# S7CAS-PLEIADES-CARTE-MERE_Pxx_FPGA_bank0.net
KiCad netlist of a schematic drawn in Altium Designer
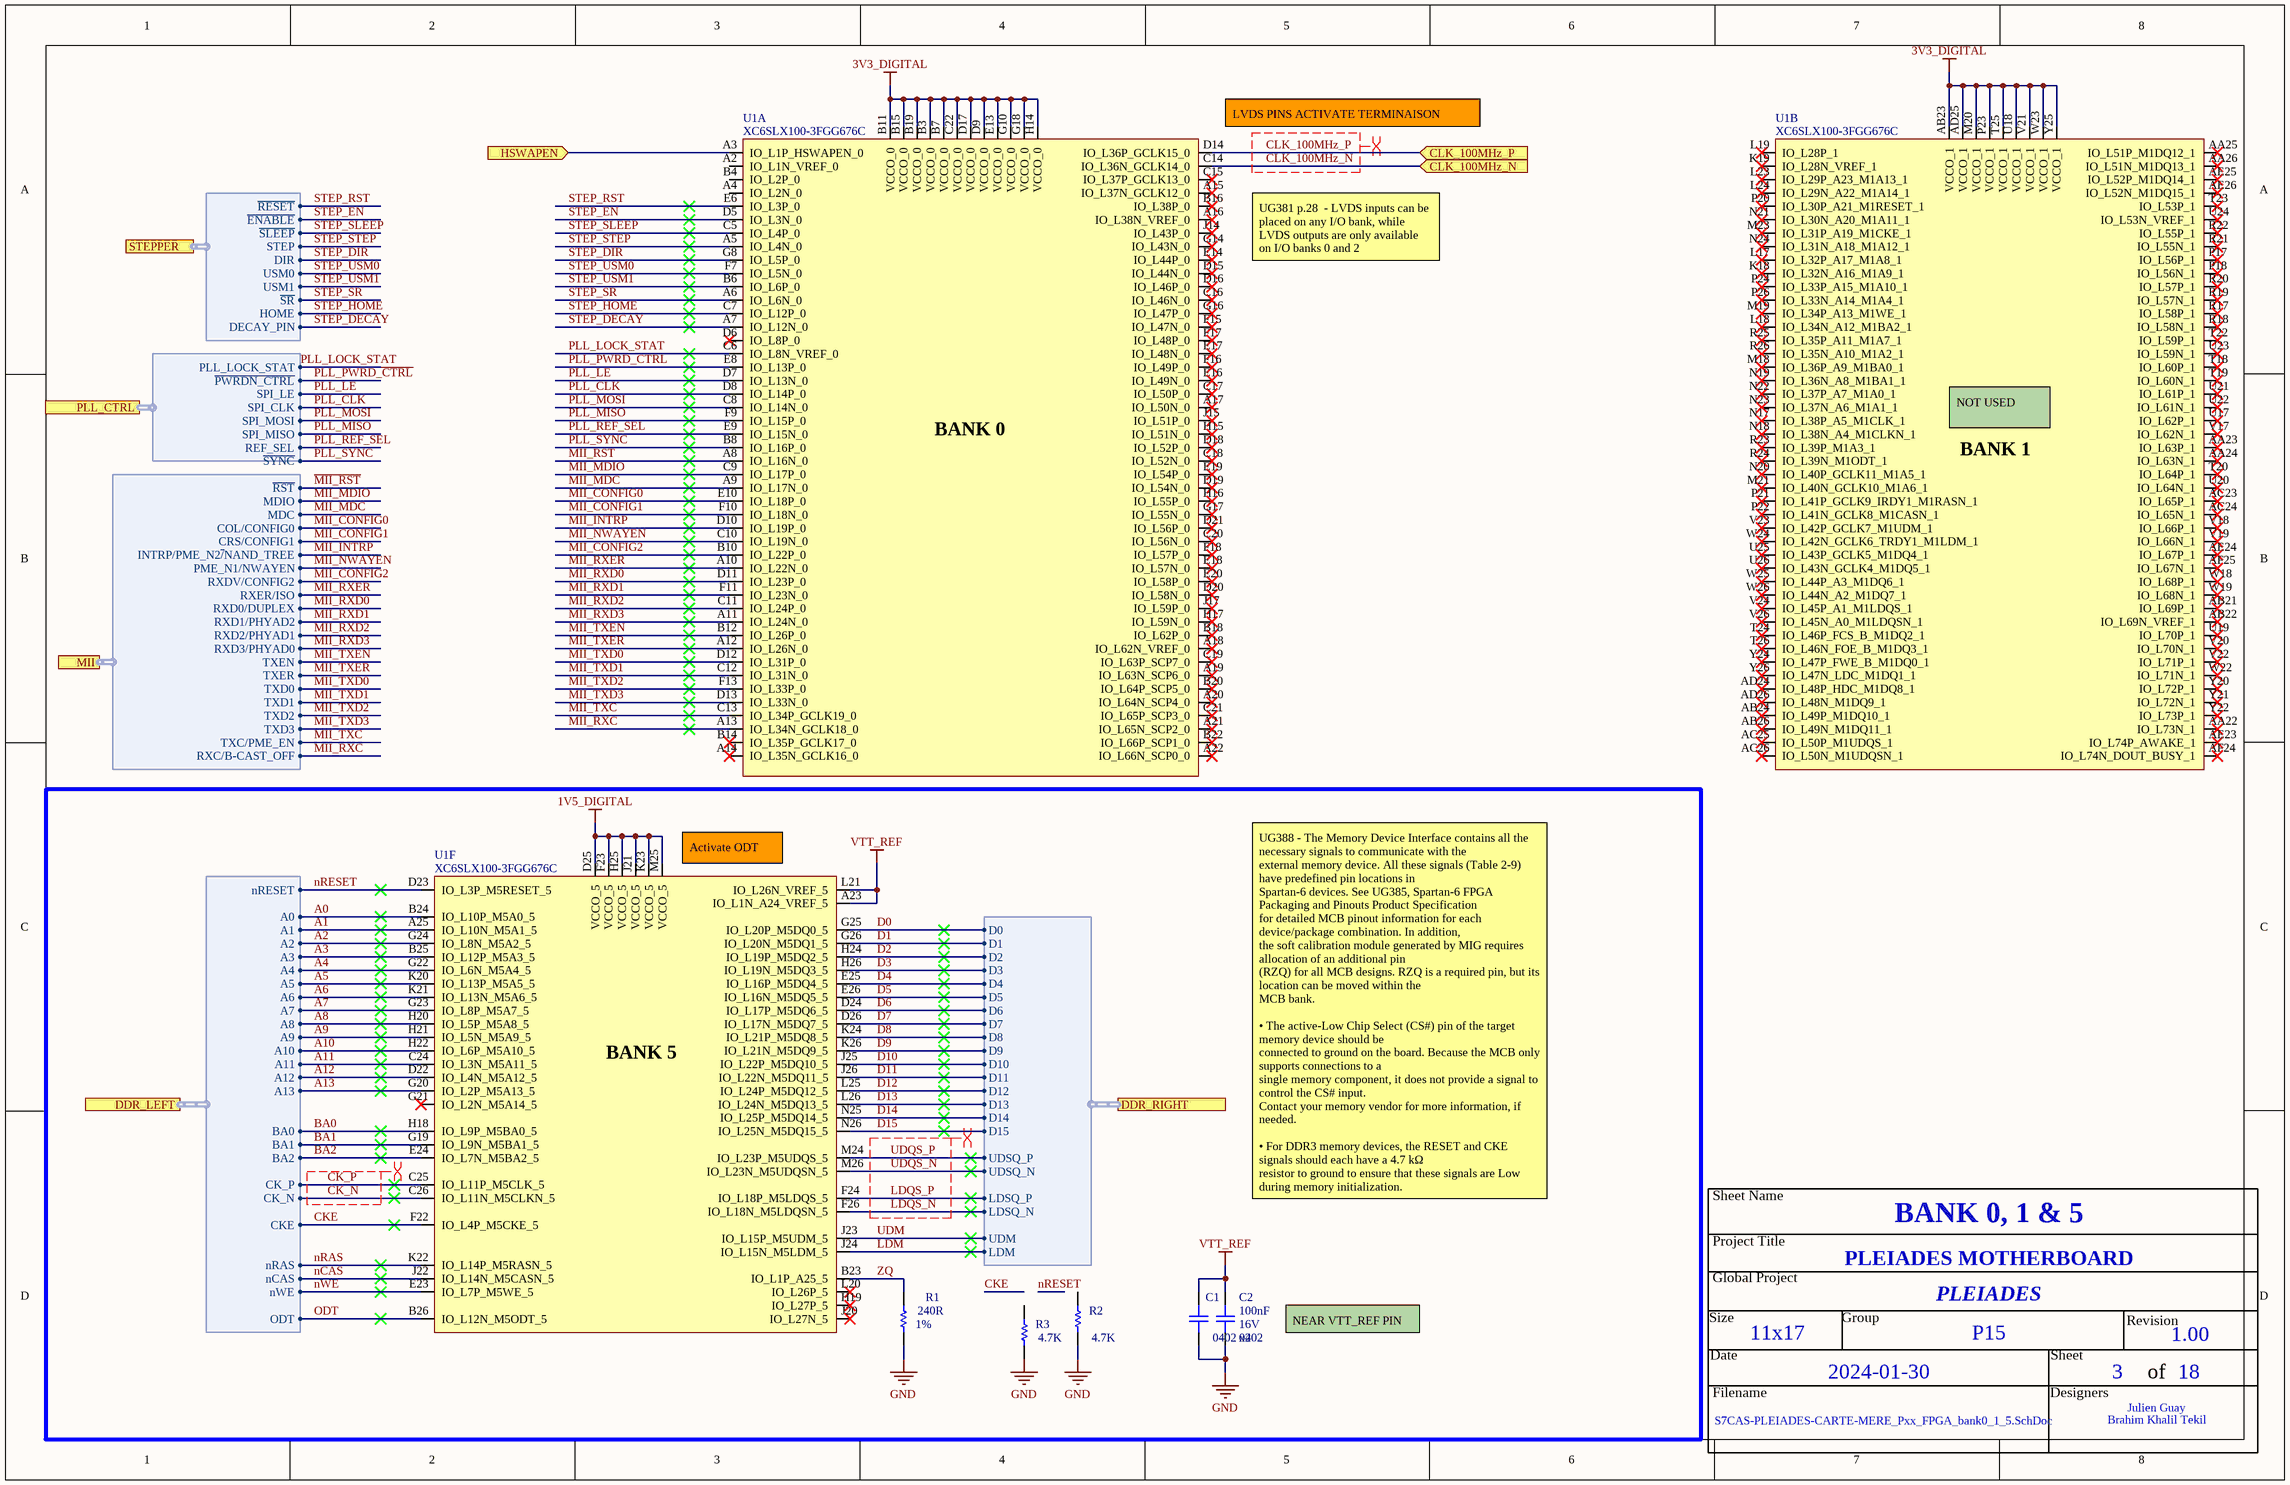
[diagram p0: S7CAS-PLEIADES-CARTE-MERE_Pxx_FPGA_bank0_1_5.SchDoc]

(export (version "E")
  (design (tool "Eeschema 10.0.6"))
  (components
    (comp (ref "C1")
      (value "0402")
      (footprint "S7CAS_LIB2023:CAP_0402")
      (description "CAP - 0402")
      (fields
        (field (name "VOLTAGE") "16V")
        (field (name "PACKAGE") "0402")
        (field (name "CREATEDBY") "Jonathan Bouchard")
      )
      (libsource (lib "S7CAS_LIB2023") (part "CAP - 0603"))
    )
    (comp (ref "C2")
      (value "100nF")
      (footprint "S7CAS_LIB2023:CAP_0402")
      (description "CAP - 0402")
      (fields
        (field (name "VOLTAGE") "16V")
        (field (name "PACKAGE") "0402")
        (field (name "Comment") "0402")
        (field (name "CREATEDBY") "Jonathan Bouchard")
      )
      (libsource (lib "S7CAS_LIB2023") (part "CAP - 0603"))
    )
    (comp (ref "R1")
      (value "240R")
      (footprint "S7CAS_LIB2023:RES_0402")
      (description "RES - 0402")
      (fields
        (field (name "PRECISION") "1%")
        (field (name "Comment") "RES - 0603")
        (field (name "CREATEDBY") "Jonathan Bouchard")
      )
      (libsource (lib "S7CAS_LIB2023") (part "RES - 0603"))
    )
    (comp (ref "R2")
      (value "4.7K")
      (footprint "S7CAS_LIB2023:RES_0402")
      (description "RES - 0402")
      (fields (field (name "Comment") "RES - 0603") (field (name "CREATEDBY") "Jonathan Bouchard"))
      (libsource (lib "S7CAS_LIB2023") (part "RES - 0603"))
    )
    (comp (ref "R3")
      (value "4.7K")
      (footprint "S7CAS_LIB2023:RES_0402")
      (description "RES - 0402")
      (fields (field (name "Comment") "RES - 0603") (field (name "CREATEDBY") "Jonathan Bouchard"))
      (libsource (lib "S7CAS_LIB2023") (part "RES - 0603"))
    )
    (comp (ref "U1")
      (value "XC6SLX100-3FGG676C")
      (footprint "FPGA_XILINX_FGG676")
      (description "FPGA - XILINX SPARTAN 6 480 I/O - BGA-676")
      (fields
        (field (name "VOLTAGE") "1.14 V ~ 1.26 V")
        (field (name "MFG") "Xilinx")
        (field (name "CREATEDBY") "Jonathan Bouchard")
      )
      (libsource (lib "S7CAS_LIB2023") (part "FPGA_XC6SLX100-3FGG676C"))
    )
  )
  (nets
    (net (code "9") (name "/A0") (class "Default")
      (node (ref "U1") (pin "B24") (pinfunction "IO_L10P_M5A0_5_B24") (pintype "passive"))
    )
    (net (code "10") (name "/A1") (class "Default")
      (node (ref "U1") (pin "A25") (pinfunction "IO_L10N_M5A1_5_A25") (pintype "passive"))
    )
    (net (code "11") (name "/A2") (class "Default")
      (node (ref "U1") (pin "G24") (pinfunction "IO_L8N_M5A2_5_G24") (pintype "passive"))
    )
    (net (code "12") (name "/A3") (class "Default")
      (node (ref "U1") (pin "B25") (pinfunction "IO_L12P_M5A3_5_B25") (pintype "passive"))
    )
    (net (code "13") (name "/A4") (class "Default")
      (node (ref "U1") (pin "G22") (pinfunction "IO_L6N_M5A4_5_G22") (pintype "passive"))
    )
    (net (code "14") (name "/A5") (class "Default")
      (node (ref "U1") (pin "K20") (pinfunction "IO_L13P_M5A5_5_K20") (pintype "passive"))
    )
    (net (code "15") (name "/A6") (class "Default")
      (node (ref "U1") (pin "K21") (pinfunction "IO_L13N_M5A6_5_K21") (pintype "passive"))
    )
    (net (code "16") (name "/A7") (class "Default")
      (node (ref "U1") (pin "G23") (pinfunction "IO_L8P_M5A7_5_G23") (pintype "passive"))
    )
    (net (code "17") (name "/A8") (class "Default")
      (node (ref "U1") (pin "H20") (pinfunction "IO_L5P_M5A8_5_H20") (pintype "passive"))
    )
    (net (code "18") (name "/A9") (class "Default")
      (node (ref "U1") (pin "H21") (pinfunction "IO_L5N_M5A9_5_H21") (pintype "passive"))
    )
    (net (code "19") (name "/A10") (class "Default")
      (node (ref "U1") (pin "H22") (pinfunction "IO_L6P_M5A10_5_H22") (pintype "passive"))
    )
    (net (code "20") (name "/A11") (class "Default")
      (node (ref "U1") (pin "C24") (pinfunction "IO_L3N_M5A11_5_C24") (pintype "passive"))
    )
    (net (code "21") (name "/A12") (class "Default")
      (node (ref "U1") (pin "D22") (pinfunction "IO_L4N_M5A12_5_D22") (pintype "passive"))
    )
    (net (code "22") (name "/A13") (class "Default")
      (node (ref "U1") (pin "G20") (pinfunction "IO_L2P_M5A13_5_G20") (pintype "passive"))
    )
    (net (code "23") (name "/BA0") (class "Default")
      (node (ref "U1") (pin "H18") (pinfunction "IO_L9P_M5BA0_5_H18") (pintype "passive"))
    )
    (net (code "24") (name "/BA1") (class "Default")
      (node (ref "U1") (pin "G19") (pinfunction "IO_L9N_M5BA1_5_G19") (pintype "passive"))
    )
    (net (code "25") (name "/BA2") (class "Default")
      (node (ref "U1") (pin "E24") (pinfunction "IO_L7N_M5BA2_5_E24") (pintype "passive"))
    )
    (net (code "26") (name "/CKE") (class "Default")
      (node (ref "U1") (pin "F22") (pinfunction "IO_L4P_M5CKE_5_F22") (pintype "passive"))
    )
    (net (code "27") (name "/CK_N") (class "Default")
      (node (ref "U1") (pin "C26") (pinfunction "IO_L11N_M5CLKN_5_C26") (pintype "passive"))
    )
    (net (code "28") (name "/CK_P") (class "Default")
      (node (ref "U1") (pin "C25") (pinfunction "IO_L11P_M5CLK_5_C25") (pintype "passive"))
    )
    (net (code "29") (name "/CLK_100MHz_N") (class "Default")
      (node (ref "U1") (pin "C14") (pinfunction "IO_L36N_GCLK14_0_C14") (pintype "passive"))
    )
    (net (code "30") (name "/CLK_100MHz_P") (class "Default")
      (node (ref "U1") (pin "D14") (pinfunction "IO_L36P_GCLK15_0_D14") (pintype "passive"))
    )
    (net (code "31") (name "/D0") (class "Default")
      (node (ref "U1") (pin "G25") (pinfunction "IO_L20P_M5DQ0_5_G25") (pintype "passive"))
    )
    (net (code "32") (name "/D1") (class "Default")
      (node (ref "U1") (pin "G26") (pinfunction "IO_L20N_M5DQ1_5_G26") (pintype "passive"))
    )
    (net (code "33") (name "/D2") (class "Default")
      (node (ref "U1") (pin "H24") (pinfunction "IO_L19P_M5DQ2_5_H24") (pintype "passive"))
    )
    (net (code "34") (name "/D3") (class "Default")
      (node (ref "U1") (pin "H26") (pinfunction "IO_L19N_M5DQ3_5_H26") (pintype "passive"))
    )
    (net (code "35") (name "/D4") (class "Default")
      (node (ref "U1") (pin "E25") (pinfunction "IO_L16P_M5DQ4_5_E25") (pintype "passive"))
    )
    (net (code "36") (name "/D5") (class "Default")
      (node (ref "U1") (pin "E26") (pinfunction "IO_L16N_M5DQ5_5_E26") (pintype "passive"))
    )
    (net (code "37") (name "/D6") (class "Default")
      (node (ref "U1") (pin "D24") (pinfunction "IO_L17P_M5DQ6_5_D24") (pintype "passive"))
    )
    (net (code "38") (name "/D7") (class "Default")
      (node (ref "U1") (pin "D26") (pinfunction "IO_L17N_M5DQ7_5_D26") (pintype "passive"))
    )
    (net (code "39") (name "/D8") (class "Default")
      (node (ref "U1") (pin "K24") (pinfunction "IO_L21P_M5DQ8_5_K24") (pintype "passive"))
    )
    (net (code "40") (name "/D9") (class "Default")
      (node (ref "U1") (pin "K26") (pinfunction "IO_L21N_M5DQ9_5_K26") (pintype "passive"))
    )
    (net (code "41") (name "/D10") (class "Default")
      (node (ref "U1") (pin "J25") (pinfunction "IO_L22P_M5DQ10_5_J25") (pintype "passive"))
    )
    (net (code "42") (name "/D11") (class "Default")
      (node (ref "U1") (pin "J26") (pinfunction "IO_L22N_M5DQ11_5_J26") (pintype "passive"))
    )
    (net (code "43") (name "/D12") (class "Default")
      (node (ref "U1") (pin "L25") (pinfunction "IO_L24P_M5DQ12_5_L25") (pintype "passive"))
    )
    (net (code "44") (name "/D13") (class "Default")
      (node (ref "U1") (pin "L26") (pinfunction "IO_L24N_M5DQ13_5_L26") (pintype "passive"))
    )
    (net (code "45") (name "/D14") (class "Default")
      (node (ref "U1") (pin "N25") (pinfunction "IO_L25P_M5DQ14_5_N25") (pintype "passive"))
    )
    (net (code "46") (name "/D15") (class "Default")
      (node (ref "U1") (pin "N26") (pinfunction "IO_L25N_M5DQ15_5_N26") (pintype "passive"))
    )
    (net (code "47") (name "/HSWAPEN") (class "Default")
      (node (ref "U1") (pin "A3") (pinfunction "IO_L1P_HSWAPEN_0_A3") (pintype "passive"))
    )
    (net (code "48") (name "/LDM") (class "Default")
      (node (ref "U1") (pin "J24") (pinfunction "IO_L15N_M5LDM_5_J24") (pintype "passive"))
    )
    (net (code "49") (name "/LDQS_N") (class "Default")
      (node (ref "U1") (pin "F26") (pinfunction "IO_L18N_M5LDQSN_5_F26") (pintype "passive"))
    )
    (net (code "50") (name "/LDQS_P") (class "Default")
      (node (ref "U1") (pin "F24") (pinfunction "IO_L18P_M5LDQS_5_F24") (pintype "passive"))
    )
    (net (code "51") (name "/MII_CONFIG0") (class "Default")
      (node (ref "U1") (pin "E10") (pinfunction "IO_L18P_0_E10") (pintype "passive"))
    )
    (net (code "52") (name "/MII_CONFIG1") (class "Default")
      (node (ref "U1") (pin "F10") (pinfunction "IO_L18N_0_F10") (pintype "passive"))
    )
    (net (code "53") (name "/MII_CONFIG2") (class "Default")
      (node (ref "U1") (pin "B10") (pinfunction "IO_L22P_0_B10") (pintype "passive"))
    )
    (net (code "54") (name "/MII_INTRP") (class "Default")
      (node (ref "U1") (pin "D10") (pinfunction "IO_L19P_0_D10") (pintype "passive"))
    )
    (net (code "55") (name "/MII_MDC") (class "Default")
      (node (ref "U1") (pin "A9") (pinfunction "IO_L17N_0_A9") (pintype "passive"))
    )
    (net (code "56") (name "/MII_MDIO") (class "Default")
      (node (ref "U1") (pin "C9") (pinfunction "IO_L17P_0_C9") (pintype "passive"))
    )
    (net (code "57") (name "/MII_NWAYEN") (class "Default")
      (node (ref "U1") (pin "C10") (pinfunction "IO_L19N_0_C10") (pintype "passive"))
    )
    (net (code "58") (name "/MII_RST") (class "Default")
      (node (ref "U1") (pin "A8") (pinfunction "IO_L16N_0_A8") (pintype "passive"))
    )
    (net (code "59") (name "/MII_RXC") (class "Default")
      (node (ref "U1") (pin "A13") (pinfunction "IO_L34N_GCLK18_0_A13") (pintype "passive"))
    )
    (net (code "60") (name "/MII_RXD0") (class "Default")
      (node (ref "U1") (pin "D11") (pinfunction "IO_L23P_0_D11") (pintype "passive"))
    )
    (net (code "61") (name "/MII_RXD1") (class "Default")
      (node (ref "U1") (pin "F11") (pinfunction "IO_L23N_0_F11") (pintype "passive"))
    )
    (net (code "62") (name "/MII_RXD2") (class "Default")
      (node (ref "U1") (pin "C11") (pinfunction "IO_L24P_0_C11") (pintype "passive"))
    )
    (net (code "63") (name "/MII_RXD3") (class "Default")
      (node (ref "U1") (pin "A11") (pinfunction "IO_L24N_0_A11") (pintype "passive"))
    )
    (net (code "64") (name "/MII_RXER") (class "Default")
      (node (ref "U1") (pin "A10") (pinfunction "IO_L22N_0_A10") (pintype "passive"))
    )
    (net (code "65") (name "/MII_TXC") (class "Default")
      (node (ref "U1") (pin "C13") (pinfunction "IO_L34P_GCLK19_0_C13") (pintype "passive"))
    )
    (net (code "66") (name "/MII_TXD0") (class "Default")
      (node (ref "U1") (pin "D12") (pinfunction "IO_L31P_0_D12") (pintype "passive"))
    )
    (net (code "67") (name "/MII_TXD1") (class "Default")
      (node (ref "U1") (pin "C12") (pinfunction "IO_L31N_0_C12") (pintype "passive"))
    )
    (net (code "68") (name "/MII_TXD2") (class "Default")
      (node (ref "U1") (pin "F13") (pinfunction "IO_L33P_0_F13") (pintype "passive"))
    )
    (net (code "69") (name "/MII_TXD3") (class "Default")
      (node (ref "U1") (pin "D13") (pinfunction "IO_L33N_0_D13") (pintype "passive"))
    )
    (net (code "70") (name "/MII_TXEN") (class "Default")
      (node (ref "U1") (pin "B12") (pinfunction "IO_L26P_0_B12") (pintype "passive"))
    )
    (net (code "71") (name "/MII_TXER") (class "Default")
      (node (ref "U1") (pin "A12") (pinfunction "IO_L26N_0_A12") (pintype "passive"))
    )
    (net (code "72") (name "/ODT") (class "Default")
      (node (ref "U1") (pin "B26") (pinfunction "IO_L12N_M5ODT_5_B26") (pintype "passive"))
    )
    (net (code "73") (name "/PLL_CLK") (class "Default")
      (node (ref "U1") (pin "D8") (pinfunction "IO_L14P_0_D8") (pintype "passive"))
    )
    (net (code "74") (name "/PLL_LE") (class "Default")
      (node (ref "U1") (pin "D7") (pinfunction "IO_L13N_0_D7") (pintype "passive"))
    )
    (net (code "75") (name "/PLL_LOCK_STAT") (class "Default")
      (node (ref "U1") (pin "C6") (pinfunction "IO_L8N_VREF_0_C6") (pintype "passive"))
    )
    (net (code "76") (name "/PLL_MISO") (class "Default")
      (node (ref "U1") (pin "F9") (pinfunction "IO_L15P_0_F9") (pintype "passive"))
    )
    (net (code "77") (name "/PLL_MOSI") (class "Default")
      (node (ref "U1") (pin "C8") (pinfunction "IO_L14N_0_C8") (pintype "passive"))
    )
    (net (code "78") (name "/PLL_PWRD_CTRL") (class "Default")
      (node (ref "U1") (pin "E8") (pinfunction "IO_L13P_0_E8") (pintype "passive"))
    )
    (net (code "79") (name "/PLL_REF_SEL") (class "Default")
      (node (ref "U1") (pin "E9") (pinfunction "IO_L15N_0_E9") (pintype "passive"))
    )
    (net (code "80") (name "/PLL_SYNC") (class "Default")
      (node (ref "U1") (pin "B8") (pinfunction "IO_L16P_0_B8") (pintype "passive"))
    )
    (net (code "81") (name "/STEP_DECAY") (class "Default")
      (node (ref "U1") (pin "A7") (pinfunction "IO_L12N_0_A7") (pintype "passive"))
    )
    (net (code "82") (name "/STEP_DIR") (class "Default")
      (node (ref "U1") (pin "G8") (pinfunction "IO_L5P_0_G8") (pintype "passive"))
    )
    (net (code "83") (name "/STEP_EN") (class "Default")
      (node (ref "U1") (pin "D5") (pinfunction "IO_L3N_0_D5") (pintype "passive"))
    )
    (net (code "84") (name "/STEP_HOME") (class "Default")
      (node (ref "U1") (pin "C7") (pinfunction "IO_L12P_0_C7") (pintype "passive"))
    )
    (net (code "85") (name "/STEP_RST") (class "Default")
      (node (ref "U1") (pin "E6") (pinfunction "IO_L3P_0_E6") (pintype "passive"))
    )
    (net (code "86") (name "/STEP_SLEEP") (class "Default")
      (node (ref "U1") (pin "C5") (pinfunction "IO_L4P_0_C5") (pintype "passive"))
    )
    (net (code "87") (name "/STEP_SR") (class "Default")
      (node (ref "U1") (pin "A6") (pinfunction "IO_L6N_0_A6") (pintype "passive"))
    )
    (net (code "88") (name "/STEP_STEP") (class "Default")
      (node (ref "U1") (pin "A5") (pinfunction "IO_L4N_0_A5") (pintype "passive"))
    )
    (net (code "89") (name "/STEP_USM0") (class "Default")
      (node (ref "U1") (pin "F7") (pinfunction "IO_L5N_0_F7") (pintype "passive"))
    )
    (net (code "90") (name "/STEP_USM1") (class "Default")
      (node (ref "U1") (pin "B6") (pinfunction "IO_L6P_0_B6") (pintype "passive"))
    )
    (net (code "91") (name "/UDM") (class "Default")
      (node (ref "U1") (pin "J23") (pinfunction "IO_L15P_M5UDM_5_J23") (pintype "passive"))
    )
    (net (code "92") (name "/UDQS_N") (class "Default")
      (node (ref "U1") (pin "M26") (pinfunction "IO_L23N_M5UDQSN_5_M26") (pintype "passive"))
    )
    (net (code "93") (name "/UDQS_P") (class "Default")
      (node (ref "U1") (pin "M24") (pinfunction "IO_L23P_M5UDQS_5_M24") (pintype "passive"))
    )
    (net (code "94") (name "/ZQ") (class "Default")
      (node (ref "R1") (pin "2") (pinfunction "2_2") (pintype "passive"))
      (node (ref "U1") (pin "B23") (pinfunction "IO_L1P_A25_5_B23") (pintype "passive"))
    )
    (net (code "95") (name "/nCAS") (class "Default")
      (node (ref "U1") (pin "J22") (pinfunction "IO_L14N_M5CASN_5_J22") (pintype "passive"))
    )
    (net (code "96") (name "/nRAS") (class "Default")
      (node (ref "U1") (pin "K22") (pinfunction "IO_L14P_M5RASN_5_K22") (pintype "passive"))
    )
    (net (code "97") (name "/nRESET") (class "Default")
      (node (ref "U1") (pin "D23") (pinfunction "IO_L3P_M5RESET_5_D23") (pintype "passive"))
    )
    (net (code "98") (name "/nWE") (class "Default")
      (node (ref "U1") (pin "E23") (pinfunction "IO_L7P_M5WE_5_E23") (pintype "passive"))
    )
    (net (code "104") (name "1V5_DIGITAL") (class "Default")
      (node (ref "U1") (pin "D25") (pinfunction "VCCO_5_D25") (pintype "passive"))
      (node (ref "U1") (pin "F23") (pinfunction "VCCO_5_F23") (pintype "passive"))
      (node (ref "U1") (pin "H25") (pinfunction "VCCO_5_H25") (pintype "passive"))
      (node (ref "U1") (pin "J21") (pinfunction "VCCO_5_J21") (pintype "passive"))
      (node (ref "U1") (pin "K23") (pinfunction "VCCO_5_K23") (pintype "passive"))
      (node (ref "U1") (pin "M25") (pinfunction "VCCO_5_M25") (pintype "passive"))
    )
    (net (code "105") (name "3V3_DIGITAL") (class "Default")
      (node (ref "U1") (pin "AB23") (pinfunction "VCCO_1_AB23") (pintype "passive"))
      (node (ref "U1") (pin "AD25") (pinfunction "VCCO_1_AD25") (pintype "passive"))
      (node (ref "U1") (pin "B11") (pinfunction "VCCO_0_B11") (pintype "passive"))
      (node (ref "U1") (pin "B15") (pinfunction "VCCO_0_B15") (pintype "passive"))
      (node (ref "U1") (pin "B19") (pinfunction "VCCO_0_B19") (pintype "passive"))
      (node (ref "U1") (pin "B3") (pinfunction "VCCO_0_B3") (pintype "passive"))
      (node (ref "U1") (pin "B7") (pinfunction "VCCO_0_B7") (pintype "passive"))
      (node (ref "U1") (pin "C22") (pinfunction "VCCO_0_C22") (pintype "passive"))
      (node (ref "U1") (pin "D17") (pinfunction "VCCO_0_D17") (pintype "passive"))
      (node (ref "U1") (pin "D9") (pinfunction "VCCO_0_D9") (pintype "passive"))
      (node (ref "U1") (pin "E13") (pinfunction "VCCO_0_E13") (pintype "passive"))
      (node (ref "U1") (pin "G10") (pinfunction "VCCO_0_G10") (pintype "passive"))
      (node (ref "U1") (pin "G18") (pinfunction "VCCO_0_G18") (pintype "passive"))
      (node (ref "U1") (pin "H14") (pinfunction "VCCO_0_H14") (pintype "passive"))
      (node (ref "U1") (pin "M20") (pinfunction "VCCO_1_M20") (pintype "passive"))
      (node (ref "U1") (pin "P23") (pinfunction "VCCO_1_P23") (pintype "passive"))
      (node (ref "U1") (pin "T25") (pinfunction "VCCO_1_T25") (pintype "passive"))
      (node (ref "U1") (pin "U18") (pinfunction "VCCO_1_U18") (pintype "passive"))
      (node (ref "U1") (pin "V21") (pinfunction "VCCO_1_V21") (pintype "passive"))
      (node (ref "U1") (pin "W23") (pinfunction "VCCO_1_W23") (pintype "passive"))
      (node (ref "U1") (pin "Y25") (pinfunction "VCCO_1_Y25") (pintype "passive"))
    )
    (net (code "106") (name "GND") (class "Default")
      (node (ref "C1") (pin "1") (pinfunction "1_1") (pintype "passive"))
      (node (ref "C2") (pin "1") (pinfunction "1_1") (pintype "passive"))
      (node (ref "R1") (pin "1") (pinfunction "1_1") (pintype "passive"))
      (node (ref "R2") (pin "1") (pinfunction "1_1") (pintype "passive"))
      (node (ref "R3") (pin "1") (pinfunction "1_1") (pintype "passive"))
    )
    (net (code "107") (name "VTT_REF") (class "Default")
      (node (ref "C1") (pin "2") (pinfunction "2_2") (pintype "passive"))
      (node (ref "C2") (pin "2") (pinfunction "2_2") (pintype "passive"))
      (node (ref "U1") (pin "A23") (pinfunction "IO_L1N_A24_VREF_5_A23") (pintype "passive"))
      (node (ref "U1") (pin "L21") (pinfunction "IO_L26N_VREF_5_L21") (pintype "passive"))
    )
    (net (code "108") (name "unconnected-(R2-Pad2)") (class "Default")
      (node (ref "R2") (pin "2") (pinfunction "2_2") (pintype "passive"))
    )
    (net (code "109") (name "unconnected-(R3-Pad2)") (class "Default")
      (node (ref "R3") (pin "2") (pinfunction "2_2") (pintype "passive"))
    )
    (net (code "110") (name "unconnected-(U1A-IO_L1N_VREF_0-PadA2)") (class "Default")
      (node (ref "U1") (pin "A2") (pinfunction "IO_L1N_VREF_0_A2") (pintype "passive"))
    )
    (net (code "111") (name "unconnected-(U1A-IO_L2N_0-PadA4)") (class "Default")
      (node (ref "U1") (pin "A4") (pinfunction "IO_L2N_0_A4") (pintype "passive"))
    )
    (net (code "112") (name "unconnected-(U1A-IO_L2P_0-PadB4)") (class "Default")
      (node (ref "U1") (pin "B4") (pinfunction "IO_L2P_0_B4") (pintype "passive"))
    )
    (net (code "113") (name "unconnected-(U1A-IO_L8P_0-PadD6)") (class "Default")
      (node (ref "U1") (pin "D6") (pinfunction "IO_L8P_0_D6") (pintype "passive+no_connect"))
    )
    (net (code "114") (name "unconnected-(U1A-IO_L35N_GCLK16_0-PadA14)") (class "Default")
      (node (ref "U1") (pin "A14") (pinfunction "IO_L35N_GCLK16_0_A14") (pintype "passive+no_connect"))
    )
    (net (code "115") (name "unconnected-(U1A-IO_L35P_GCLK17_0-PadB14)") (class "Default")
      (node (ref "U1") (pin "B14") (pinfunction "IO_L35P_GCLK17_0_B14") (pintype "passive+no_connect"))
    )
    (net (code "116") (name "unconnected-(U1A-IO_L37N_GCLK12_0-PadA15)") (class "Default")
      (node (ref "U1") (pin "A15") (pinfunction "IO_L37N_GCLK12_0_A15") (pintype "passive+no_connect"))
    )
    (net (code "117") (name "unconnected-(U1A-IO_L37P_GCLK13_0-PadC15)") (class "Default")
      (node (ref "U1") (pin "C15") (pinfunction "IO_L37P_GCLK13_0_C15") (pintype "passive+no_connect"))
    )
    (net (code "118") (name "unconnected-(U1A-IO_L38N_VREF_0-PadA16)") (class "Default")
      (node (ref "U1") (pin "A16") (pinfunction "IO_L38N_VREF_0_A16") (pintype "passive+no_connect"))
    )
    (net (code "119") (name "unconnected-(U1A-IO_L38P_0-PadB16)") (class "Default")
      (node (ref "U1") (pin "B16") (pinfunction "IO_L38P_0_B16") (pintype "passive+no_connect"))
    )
    (net (code "120") (name "unconnected-(U1A-IO_L43N_0-PadG14)") (class "Default")
      (node (ref "U1") (pin "G14") (pinfunction "IO_L43N_0_G14") (pintype "passive+no_connect"))
    )
    (net (code "121") (name "unconnected-(U1A-IO_L43P_0-PadJ14)") (class "Default")
      (node (ref "U1") (pin "J14") (pinfunction "IO_L43P_0_J14") (pintype "passive+no_connect"))
    )
    (net (code "122") (name "unconnected-(U1A-IO_L44N_0-PadD15)") (class "Default")
      (node (ref "U1") (pin "D15") (pinfunction "IO_L44N_0_D15") (pintype "passive+no_connect"))
    )
    (net (code "123") (name "unconnected-(U1A-IO_L44P_0-PadE14)") (class "Default")
      (node (ref "U1") (pin "E14") (pinfunction "IO_L44P_0_E14") (pintype "passive+no_connect"))
    )
    (net (code "124") (name "unconnected-(U1A-IO_L46N_0-PadC16)") (class "Default")
      (node (ref "U1") (pin "C16") (pinfunction "IO_L46N_0_C16") (pintype "passive+no_connect"))
    )
    (net (code "125") (name "unconnected-(U1A-IO_L46P_0-PadD16)") (class "Default")
      (node (ref "U1") (pin "D16") (pinfunction "IO_L46P_0_D16") (pintype "passive+no_connect"))
    )
    (net (code "126") (name "unconnected-(U1A-IO_L47N_0-PadF15)") (class "Default")
      (node (ref "U1") (pin "F15") (pinfunction "IO_L47N_0_F15") (pintype "passive+no_connect"))
    )
    (net (code "127") (name "unconnected-(U1A-IO_L47P_0-PadG16)") (class "Default")
      (node (ref "U1") (pin "G16") (pinfunction "IO_L47P_0_G16") (pintype "passive+no_connect"))
    )
    (net (code "128") (name "unconnected-(U1A-IO_L48N_0-PadE17)") (class "Default")
      (node (ref "U1") (pin "E17") (pinfunction "IO_L48N_0_E17") (pintype "passive+no_connect"))
    )
    (net (code "129") (name "unconnected-(U1A-IO_L48P_0-PadF17)") (class "Default")
      (node (ref "U1") (pin "F17") (pinfunction "IO_L48P_0_F17") (pintype "passive+no_connect"))
    )
    (net (code "130") (name "unconnected-(U1A-IO_L49N_0-PadE16)") (class "Default")
      (node (ref "U1") (pin "E16") (pinfunction "IO_L49N_0_E16") (pintype "passive+no_connect"))
    )
    (net (code "131") (name "unconnected-(U1A-IO_L49P_0-PadF16)") (class "Default")
      (node (ref "U1") (pin "F16") (pinfunction "IO_L49P_0_F16") (pintype "passive+no_connect"))
    )
    (net (code "132") (name "unconnected-(U1A-IO_L50N_0-PadA17)") (class "Default")
      (node (ref "U1") (pin "A17") (pinfunction "IO_L50N_0_A17") (pintype "passive+no_connect"))
    )
    (net (code "133") (name "unconnected-(U1A-IO_L50P_0-PadC17)") (class "Default")
      (node (ref "U1") (pin "C17") (pinfunction "IO_L50P_0_C17") (pintype "passive+no_connect"))
    )
    (net (code "134") (name "unconnected-(U1A-IO_L51N_0-PadH15)") (class "Default")
      (node (ref "U1") (pin "H15") (pinfunction "IO_L51N_0_H15") (pintype "passive+no_connect"))
    )
    (net (code "135") (name "unconnected-(U1A-IO_L51P_0-PadJ15)") (class "Default")
      (node (ref "U1") (pin "J15") (pinfunction "IO_L51P_0_J15") (pintype "passive+no_connect"))
    )
    (net (code "136") (name "unconnected-(U1A-IO_L52N_0-PadC18)") (class "Default")
      (node (ref "U1") (pin "C18") (pinfunction "IO_L52N_0_C18") (pintype "passive+no_connect"))
    )
    (net (code "137") (name "unconnected-(U1A-IO_L52P_0-PadD18)") (class "Default")
      (node (ref "U1") (pin "D18") (pinfunction "IO_L52P_0_D18") (pintype "passive+no_connect"))
    )
    (net (code "138") (name "unconnected-(U1A-IO_L54N_0-PadD19)") (class "Default")
      (node (ref "U1") (pin "D19") (pinfunction "IO_L54N_0_D19") (pintype "passive+no_connect"))
    )
    (net (code "139") (name "unconnected-(U1A-IO_L54P_0-PadE19)") (class "Default")
      (node (ref "U1") (pin "E19") (pinfunction "IO_L54P_0_E19") (pintype "passive+no_connect"))
    )
    (net (code "140") (name "unconnected-(U1A-IO_L55N_0-PadG17)") (class "Default")
      (node (ref "U1") (pin "G17") (pinfunction "IO_L55N_0_G17") (pintype "passive+no_connect"))
    )
    (net (code "141") (name "unconnected-(U1A-IO_L55P_0-PadH16)") (class "Default")
      (node (ref "U1") (pin "H16") (pinfunction "IO_L55P_0_H16") (pintype "passive+no_connect"))
    )
    (net (code "142") (name "unconnected-(U1A-IO_L56N_0-PadC20)") (class "Default")
      (node (ref "U1") (pin "C20") (pinfunction "IO_L56N_0_C20") (pintype "passive+no_connect"))
    )
    (net (code "143") (name "unconnected-(U1A-IO_L56P_0-PadD21)") (class "Default")
      (node (ref "U1") (pin "D21") (pinfunction "IO_L56P_0_D21") (pintype "passive+no_connect"))
    )
    (net (code "144") (name "unconnected-(U1A-IO_L57N_0-PadE18)") (class "Default")
      (node (ref "U1") (pin "E18") (pinfunction "IO_L57N_0_E18") (pintype "passive+no_connect"))
    )
    (net (code "145") (name "unconnected-(U1A-IO_L57P_0-PadF18)") (class "Default")
      (node (ref "U1") (pin "F18") (pinfunction "IO_L57P_0_F18") (pintype "passive+no_connect"))
    )
    (net (code "146") (name "unconnected-(U1A-IO_L58N_0-PadD20)") (class "Default")
      (node (ref "U1") (pin "D20") (pinfunction "IO_L58N_0_D20") (pintype "passive+no_connect"))
    )
    (net (code "147") (name "unconnected-(U1A-IO_L58P_0-PadE20)") (class "Default")
      (node (ref "U1") (pin "E20") (pinfunction "IO_L58P_0_E20") (pintype "passive+no_connect"))
    )
    (net (code "148") (name "unconnected-(U1A-IO_L59N_0-PadH17)") (class "Default")
      (node (ref "U1") (pin "H17") (pinfunction "IO_L59N_0_H17") (pintype "passive+no_connect"))
    )
    (net (code "149") (name "unconnected-(U1A-IO_L59P_0-PadJ17)") (class "Default")
      (node (ref "U1") (pin "J17") (pinfunction "IO_L59P_0_J17") (pintype "passive+no_connect"))
    )
    (net (code "150") (name "unconnected-(U1A-IO_L62N_VREF_0-PadA18)") (class "Default")
      (node (ref "U1") (pin "A18") (pinfunction "IO_L62N_VREF_0_A18") (pintype "passive+no_connect"))
    )
    (net (code "151") (name "unconnected-(U1A-IO_L62P_0-PadB18)") (class "Default")
      (node (ref "U1") (pin "B18") (pinfunction "IO_L62P_0_B18") (pintype "passive+no_connect"))
    )
    (net (code "152") (name "unconnected-(U1A-IO_L63N_SCP6_0-PadA19)") (class "Default")
      (node (ref "U1") (pin "A19") (pinfunction "IO_L63N_SCP6_0_A19") (pintype "passive+no_connect"))
    )
    (net (code "153") (name "unconnected-(U1A-IO_L63P_SCP7_0-PadC19)") (class "Default")
      (node (ref "U1") (pin "C19") (pinfunction "IO_L63P_SCP7_0_C19") (pintype "passive+no_connect"))
    )
    (net (code "154") (name "unconnected-(U1A-IO_L64N_SCP4_0-PadA20)") (class "Default")
      (node (ref "U1") (pin "A20") (pinfunction "IO_L64N_SCP4_0_A20") (pintype "passive+no_connect"))
    )
    (net (code "155") (name "unconnected-(U1A-IO_L64P_SCP5_0-PadB20)") (class "Default")
      (node (ref "U1") (pin "B20") (pinfunction "IO_L64P_SCP5_0_B20") (pintype "passive+no_connect"))
    )
    (net (code "156") (name "unconnected-(U1A-IO_L65N_SCP2_0-PadA21)") (class "Default")
      (node (ref "U1") (pin "A21") (pinfunction "IO_L65N_SCP2_0_A21") (pintype "passive+no_connect"))
    )
    (net (code "157") (name "unconnected-(U1A-IO_L65P_SCP3_0-PadC21)") (class "Default")
      (node (ref "U1") (pin "C21") (pinfunction "IO_L65P_SCP3_0_C21") (pintype "passive+no_connect"))
    )
    (net (code "158") (name "unconnected-(U1A-IO_L66N_SCP0_0-PadA22)") (class "Default")
      (node (ref "U1") (pin "A22") (pinfunction "IO_L66N_SCP0_0_A22") (pintype "passive+no_connect"))
    )
    (net (code "159") (name "unconnected-(U1A-IO_L66P_SCP1_0-PadB22)") (class "Default")
      (node (ref "U1") (pin "B22") (pinfunction "IO_L66P_SCP1_0_B22") (pintype "passive+no_connect"))
    )
    (net (code "160") (name "unconnected-(U1B-IO_L28N_VREF_1-PadK19)") (class "Default")
      (node (ref "U1") (pin "K19") (pinfunction "IO_L28N_VREF_1_K19") (pintype "passive+no_connect"))
    )
    (net (code "161") (name "unconnected-(U1B-IO_L28P_1-PadL19)") (class "Default")
      (node (ref "U1") (pin "L19") (pinfunction "IO_L28P_1_L19") (pintype "passive+no_connect"))
    )
    (net (code "162") (name "unconnected-(U1B-IO_L29N_A22_M1A14_1-PadL24)") (class "Default")
      (node (ref "U1") (pin "L24") (pinfunction "IO_L29N_A22_M1A14_1_L24") (pintype "passive+no_connect"))
    )
    (net (code "163") (name "unconnected-(U1B-IO_L29P_A23_M1A13_1-PadL23)") (class "Default")
      (node (ref "U1") (pin "L23") (pinfunction "IO_L29P_A23_M1A13_1_L23") (pintype "passive+no_connect"))
    )
    (net (code "164") (name "unconnected-(U1B-IO_L30N_A20_M1A11_1-PadN21)") (class "Default")
      (node (ref "U1") (pin "N21") (pinfunction "IO_L30N_A20_M1A11_1_N21") (pintype "passive+no_connect"))
    )
    (net (code "165") (name "unconnected-(U1B-IO_L30P_A21_M1RESET_1-PadP20)") (class "Default")
      (node (ref "U1") (pin "P20") (pinfunction "IO_L30P_A21_M1RESET_1_P20") (pintype "passive+no_connect"))
    )
    (net (code "166") (name "unconnected-(U1B-IO_L31N_A18_M1A12_1-PadN24)") (class "Default")
      (node (ref "U1") (pin "N24") (pinfunction "IO_L31N_A18_M1A12_1_N24") (pintype "passive+no_connect"))
    )
    (net (code "167") (name "unconnected-(U1B-IO_L31P_A19_M1CKE_1-PadM23)") (class "Default")
      (node (ref "U1") (pin "M23") (pinfunction "IO_L31P_A19_M1CKE_1_M23") (pintype "passive+no_connect"))
    )
    (net (code "168") (name "unconnected-(U1B-IO_L32N_A16_M1A9_1-PadK18)") (class "Default")
      (node (ref "U1") (pin "K18") (pinfunction "IO_L32N_A16_M1A9_1_K18") (pintype "passive+no_connect"))
    )
    (net (code "169") (name "unconnected-(U1B-IO_L32P_A17_M1A8_1-PadL17)") (class "Default")
      (node (ref "U1") (pin "L17") (pinfunction "IO_L32P_A17_M1A8_1_L17") (pintype "passive+no_connect"))
    )
    (net (code "170") (name "unconnected-(U1B-IO_L33N_A14_M1A4_1-PadP26)") (class "Default")
      (node (ref "U1") (pin "P26") (pinfunction "IO_L33N_A14_M1A4_1_P26") (pintype "passive+no_connect"))
    )
    (net (code "171") (name "unconnected-(U1B-IO_L33P_A15_M1A10_1-PadP24)") (class "Default")
      (node (ref "U1") (pin "P24") (pinfunction "IO_L33P_A15_M1A10_1_P24") (pintype "passive+no_connect"))
    )
    (net (code "172") (name "unconnected-(U1B-IO_L34N_A12_M1BA2_1-PadL18)") (class "Default")
      (node (ref "U1") (pin "L18") (pinfunction "IO_L34N_A12_M1BA2_1_L18") (pintype "passive+no_connect"))
    )
    (net (code "173") (name "unconnected-(U1B-IO_L34P_A13_M1WE_1-PadM19)") (class "Default")
      (node (ref "U1") (pin "M19") (pinfunction "IO_L34P_A13_M1WE_1_M19") (pintype "passive+no_connect"))
    )
    (net (code "174") (name "unconnected-(U1B-IO_L35N_A10_M1A2_1-PadR26)") (class "Default")
      (node (ref "U1") (pin "R26") (pinfunction "IO_L35N_A10_M1A2_1_R26") (pintype "passive+no_connect"))
    )
    (net (code "175") (name "unconnected-(U1B-IO_L35P_A11_M1A7_1-PadR25)") (class "Default")
      (node (ref "U1") (pin "R25") (pinfunction "IO_L35P_A11_M1A7_1_R25") (pintype "passive+no_connect"))
    )
    (net (code "176") (name "unconnected-(U1B-IO_L36N_A8_M1BA1_1-PadN19)") (class "Default")
      (node (ref "U1") (pin "N19") (pinfunction "IO_L36N_A8_M1BA1_1_N19") (pintype "passive+no_connect"))
    )
    (net (code "177") (name "unconnected-(U1B-IO_L36P_A9_M1BA0_1-PadM18)") (class "Default")
      (node (ref "U1") (pin "M18") (pinfunction "IO_L36P_A9_M1BA0_1_M18") (pintype "passive+no_connect"))
    )
    (net (code "178") (name "unconnected-(U1B-IO_L37N_A6_M1A1_1-PadN23)") (class "Default")
      (node (ref "U1") (pin "N23") (pinfunction "IO_L37N_A6_M1A1_1_N23") (pintype "passive+no_connect"))
    )
    (net (code "179") (name "unconnected-(U1B-IO_L37P_A7_M1A0_1-PadN22)") (class "Default")
      (node (ref "U1") (pin "N22") (pinfunction "IO_L37P_A7_M1A0_1_N22") (pintype "passive+no_connect"))
    )
    (net (code "180") (name "unconnected-(U1B-IO_L38N_A4_M1CLKN_1-PadN18)") (class "Default")
      (node (ref "U1") (pin "N18") (pinfunction "IO_L38N_A4_M1CLKN_1_N18") (pintype "passive+no_connect"))
    )
    (net (code "181") (name "unconnected-(U1B-IO_L38P_A5_M1CLK_1-PadN17)") (class "Default")
      (node (ref "U1") (pin "N17") (pinfunction "IO_L38P_A5_M1CLK_1_N17") (pintype "passive+no_connect"))
    )
    (net (code "182") (name "unconnected-(U1B-IO_L39N_M1ODT_1-PadR24)") (class "Default")
      (node (ref "U1") (pin "R24") (pinfunction "IO_L39N_M1ODT_1_R24") (pintype "passive+no_connect"))
    )
    (net (code "183") (name "unconnected-(U1B-IO_L39P_M1A3_1-PadR23)") (class "Default")
      (node (ref "U1") (pin "R23") (pinfunction "IO_L39P_M1A3_1_R23") (pintype "passive+no_connect"))
    )
    (net (code "184") (name "unconnected-(U1B-IO_L40N_GCLK10_M1A6_1-PadM21)") (class "Default")
      (node (ref "U1") (pin "M21") (pinfunction "IO_L40N_GCLK10_M1A6_1_M21") (pintype "passive+no_connect"))
    )
    (net (code "185") (name "unconnected-(U1B-IO_L40P_GCLK11_M1A5_1-PadN20)") (class "Default")
      (node (ref "U1") (pin "N20") (pinfunction "IO_L40P_GCLK11_M1A5_1_N20") (pintype "passive+no_connect"))
    )
    (net (code "186") (name "unconnected-(U1B-IO_L41N_GCLK8_M1CASN_1-PadP22)") (class "Default")
      (node (ref "U1") (pin "P22") (pinfunction "IO_L41N_GCLK8_M1CASN_1_P22") (pintype "passive+no_connect"))
    )
    (net (code "187") (name "unconnected-(U1B-IO_L41P_GCLK9_IRDY1_M1RASN_1-PadP21)") (class "Default")
      (node (ref "U1") (pin "P21") (pinfunction "IO_L41P_GCLK9_IRDY1_M1RASN_1_P21") (pintype "passive+no_connect"))
    )
    (net (code "188") (name "unconnected-(U1B-IO_L42N_GCLK6_TRDY1_M1LDM_1-PadW24)") (class "Default")
      (node (ref "U1") (pin "W24") (pinfunction "IO_L42N_GCLK6_TRDY1_M1LDM_1_W24") (pintype "passive+no_connect"))
    )
    (net (code "189") (name "unconnected-(U1B-IO_L42P_GCLK7_M1UDM_1-PadV23)") (class "Default")
      (node (ref "U1") (pin "V23") (pinfunction "IO_L42P_GCLK7_M1UDM_1_V23") (pintype "passive+no_connect"))
    )
    (net (code "190") (name "unconnected-(U1B-IO_L43N_GCLK4_M1DQ5_1-PadU26)") (class "Default")
      (node (ref "U1") (pin "U26") (pinfunction "IO_L43N_GCLK4_M1DQ5_1_U26") (pintype "passive+no_connect"))
    )
    (net (code "191") (name "unconnected-(U1B-IO_L43P_GCLK5_M1DQ4_1-PadU25)") (class "Default")
      (node (ref "U1") (pin "U25") (pinfunction "IO_L43P_GCLK5_M1DQ4_1_U25") (pintype "passive+no_connect"))
    )
    (net (code "192") (name "unconnected-(U1B-IO_L44N_A2_M1DQ7_1-PadW26)") (class "Default")
      (node (ref "U1") (pin "W26") (pinfunction "IO_L44N_A2_M1DQ7_1_W26") (pintype "passive+no_connect"))
    )
    (net (code "193") (name "unconnected-(U1B-IO_L44P_A3_M1DQ6_1-PadW25)") (class "Default")
      (node (ref "U1") (pin "W25") (pinfunction "IO_L44P_A3_M1DQ6_1_W25") (pintype "passive+no_connect"))
    )
    (net (code "194") (name "unconnected-(U1B-IO_L45N_A0_M1LDQSN_1-PadV26)") (class "Default")
      (node (ref "U1") (pin "V26") (pinfunction "IO_L45N_A0_M1LDQSN_1_V26") (pintype "passive+no_connect"))
    )
    (net (code "195") (name "unconnected-(U1B-IO_L45P_A1_M1LDQS_1-PadV24)") (class "Default")
      (node (ref "U1") (pin "V24") (pinfunction "IO_L45P_A1_M1LDQS_1_V24") (pintype "passive+no_connect"))
    )
    (net (code "196") (name "unconnected-(U1B-IO_L46N_FOE_B_M1DQ3_1-PadT26)") (class "Default")
      (node (ref "U1") (pin "T26") (pinfunction "IO_L46N_FOE_B_M1DQ3_1_T26") (pintype "passive+no_connect"))
    )
    (net (code "197") (name "unconnected-(U1B-IO_L46P_FCS_B_M1DQ2_1-PadT24)") (class "Default")
      (node (ref "U1") (pin "T24") (pinfunction "IO_L46P_FCS_B_M1DQ2_1_T24") (pintype "passive+no_connect"))
    )
    (net (code "198") (name "unconnected-(U1B-IO_L47N_LDC_M1DQ1_1-PadY26)") (class "Default")
      (node (ref "U1") (pin "Y26") (pinfunction "IO_L47N_LDC_M1DQ1_1_Y26") (pintype "passive+no_connect"))
    )
    (net (code "199") (name "unconnected-(U1B-IO_L47P_FWE_B_M1DQ0_1-PadY24)") (class "Default")
      (node (ref "U1") (pin "Y24") (pinfunction "IO_L47P_FWE_B_M1DQ0_1_Y24") (pintype "passive+no_connect"))
    )
    (net (code "200") (name "unconnected-(U1B-IO_L48N_M1DQ9_1-PadAD26)") (class "Default")
      (node (ref "U1") (pin "AD26") (pinfunction "IO_L48N_M1DQ9_1_AD26") (pintype "passive+no_connect"))
    )
    (net (code "201") (name "unconnected-(U1B-IO_L48P_HDC_M1DQ8_1-PadAD24)") (class "Default")
      (node (ref "U1") (pin "AD24") (pinfunction "IO_L48P_HDC_M1DQ8_1_AD24") (pintype "passive+no_connect"))
    )
    (net (code "202") (name "unconnected-(U1B-IO_L49N_M1DQ11_1-PadAB26)") (class "Default")
      (node (ref "U1") (pin "AB26") (pinfunction "IO_L49N_M1DQ11_1_AB26") (pintype "passive+no_connect"))
    )
    (net (code "203") (name "unconnected-(U1B-IO_L49P_M1DQ10_1-PadAB24)") (class "Default")
      (node (ref "U1") (pin "AB24") (pinfunction "IO_L49P_M1DQ10_1_AB24") (pintype "passive+no_connect"))
    )
    (net (code "204") (name "unconnected-(U1B-IO_L50N_M1UDQSN_1-PadAC26)") (class "Default")
      (node (ref "U1") (pin "AC26") (pinfunction "IO_L50N_M1UDQSN_1_AC26") (pintype "passive+no_connect"))
    )
    (net (code "205") (name "unconnected-(U1B-IO_L50P_M1UDQS_1-PadAC25)") (class "Default")
      (node (ref "U1") (pin "AC25") (pinfunction "IO_L50P_M1UDQS_1_AC25") (pintype "passive+no_connect"))
    )
    (net (code "206") (name "unconnected-(U1B-IO_L51N_M1DQ13_1-PadAA26)") (class "Default")
      (node (ref "U1") (pin "AA26") (pinfunction "IO_L51N_M1DQ13_1_AA26") (pintype "passive+no_connect"))
    )
    (net (code "207") (name "unconnected-(U1B-IO_L51P_M1DQ12_1-PadAA25)") (class "Default")
      (node (ref "U1") (pin "AA25") (pinfunction "IO_L51P_M1DQ12_1_AA25") (pintype "passive+no_connect"))
    )
    (net (code "208") (name "unconnected-(U1B-IO_L52N_M1DQ15_1-PadAE26)") (class "Default")
      (node (ref "U1") (pin "AE26") (pinfunction "IO_L52N_M1DQ15_1_AE26") (pintype "passive+no_connect"))
    )
    (net (code "209") (name "unconnected-(U1B-IO_L52P_M1DQ14_1-PadAE25)") (class "Default")
      (node (ref "U1") (pin "AE25") (pinfunction "IO_L52P_M1DQ14_1_AE25") (pintype "passive+no_connect"))
    )
    (net (code "210") (name "unconnected-(U1B-IO_L53N_VREF_1-PadU24)") (class "Default")
      (node (ref "U1") (pin "U24") (pinfunction "IO_L53N_VREF_1_U24") (pintype "passive+no_connect"))
    )
    (net (code "211") (name "unconnected-(U1B-IO_L53P_1-PadT23)") (class "Default")
      (node (ref "U1") (pin "T23") (pinfunction "IO_L53P_1_T23") (pintype "passive+no_connect"))
    )
    (net (code "212") (name "unconnected-(U1B-IO_L55N_1-PadR21)") (class "Default")
      (node (ref "U1") (pin "R21") (pinfunction "IO_L55N_1_R21") (pintype "passive+no_connect"))
    )
    (net (code "213") (name "unconnected-(U1B-IO_L55P_1-PadR22)") (class "Default")
      (node (ref "U1") (pin "R22") (pinfunction "IO_L55P_1_R22") (pintype "passive+no_connect"))
    )
    (net (code "214") (name "unconnected-(U1B-IO_L56N_1-PadP18)") (class "Default")
      (node (ref "U1") (pin "P18") (pinfunction "IO_L56N_1_P18") (pintype "passive+no_connect"))
    )
    (net (code "215") (name "unconnected-(U1B-IO_L56P_1-PadP17)") (class "Default")
      (node (ref "U1") (pin "P17") (pinfunction "IO_L56P_1_P17") (pintype "passive+no_connect"))
    )
    (net (code "216") (name "unconnected-(U1B-IO_L57N_1-PadR19)") (class "Default")
      (node (ref "U1") (pin "R19") (pinfunction "IO_L57N_1_R19") (pintype "passive+no_connect"))
    )
    (net (code "217") (name "unconnected-(U1B-IO_L57P_1-PadR20)") (class "Default")
      (node (ref "U1") (pin "R20") (pinfunction "IO_L57P_1_R20") (pintype "passive+no_connect"))
    )
    (net (code "218") (name "unconnected-(U1B-IO_L58N_1-PadR18)") (class "Default")
      (node (ref "U1") (pin "R18") (pinfunction "IO_L58N_1_R18") (pintype "passive+no_connect"))
    )
    (net (code "219") (name "unconnected-(U1B-IO_L58P_1-PadR17)") (class "Default")
      (node (ref "U1") (pin "R17") (pinfunction "IO_L58P_1_R17") (pintype "passive+no_connect"))
    )
    (net (code "220") (name "unconnected-(U1B-IO_L59N_1-PadU23)") (class "Default")
      (node (ref "U1") (pin "U23") (pinfunction "IO_L59N_1_U23") (pintype "passive+no_connect"))
    )
    (net (code "221") (name "unconnected-(U1B-IO_L59P_1-PadT22)") (class "Default")
      (node (ref "U1") (pin "T22") (pinfunction "IO_L59P_1_T22") (pintype "passive+no_connect"))
    )
    (net (code "222") (name "unconnected-(U1B-IO_L60N_1-PadT19)") (class "Default")
      (node (ref "U1") (pin "T19") (pinfunction "IO_L60N_1_T19") (pintype "passive+no_connect"))
    )
    (net (code "223") (name "unconnected-(U1B-IO_L60P_1-PadT18)") (class "Default")
      (node (ref "U1") (pin "T18") (pinfunction "IO_L60P_1_T18") (pintype "passive+no_connect"))
    )
    (net (code "224") (name "unconnected-(U1B-IO_L61N_1-PadU22)") (class "Default")
      (node (ref "U1") (pin "U22") (pinfunction "IO_L61N_1_U22") (pintype "passive+no_connect"))
    )
    (net (code "225") (name "unconnected-(U1B-IO_L61P_1-PadU21)") (class "Default")
      (node (ref "U1") (pin "U21") (pinfunction "IO_L61P_1_U21") (pintype "passive+no_connect"))
    )
    (net (code "226") (name "unconnected-(U1B-IO_L62N_1-PadV17)") (class "Default")
      (node (ref "U1") (pin "V17") (pinfunction "IO_L62N_1_V17") (pintype "passive+no_connect"))
    )
    (net (code "227") (name "unconnected-(U1B-IO_L62P_1-PadU17)") (class "Default")
      (node (ref "U1") (pin "U17") (pinfunction "IO_L62P_1_U17") (pintype "passive+no_connect"))
    )
    (net (code "228") (name "unconnected-(U1B-IO_L63N_1-PadAA24)") (class "Default")
      (node (ref "U1") (pin "AA24") (pinfunction "IO_L63N_1_AA24") (pintype "passive+no_connect"))
    )
    (net (code "229") (name "unconnected-(U1B-IO_L63P_1-PadAA23)") (class "Default")
      (node (ref "U1") (pin "AA23") (pinfunction "IO_L63P_1_AA23") (pintype "passive+no_connect"))
    )
    (net (code "230") (name "unconnected-(U1B-IO_L64N_1-PadU20)") (class "Default")
      (node (ref "U1") (pin "U20") (pinfunction "IO_L64N_1_U20") (pintype "passive+no_connect"))
    )
    (net (code "231") (name "unconnected-(U1B-IO_L64P_1-PadT20)") (class "Default")
      (node (ref "U1") (pin "T20") (pinfunction "IO_L64P_1_T20") (pintype "passive+no_connect"))
    )
    (net (code "232") (name "unconnected-(U1B-IO_L65N_1-PadAC24)") (class "Default")
      (node (ref "U1") (pin "AC24") (pinfunction "IO_L65N_1_AC24") (pintype "passive+no_connect"))
    )
    (net (code "233") (name "unconnected-(U1B-IO_L65P_1-PadAC23)") (class "Default")
      (node (ref "U1") (pin "AC23") (pinfunction "IO_L65P_1_AC23") (pintype "passive+no_connect"))
    )
    (net (code "234") (name "unconnected-(U1B-IO_L66N_1-PadV19)") (class "Default")
      (node (ref "U1") (pin "V19") (pinfunction "IO_L66N_1_V19") (pintype "passive+no_connect"))
    )
    (net (code "235") (name "unconnected-(U1B-IO_L66P_1-PadV18)") (class "Default")
      (node (ref "U1") (pin "V18") (pinfunction "IO_L66P_1_V18") (pintype "passive+no_connect"))
    )
    (net (code "236") (name "unconnected-(U1B-IO_L67N_1-PadAF25)") (class "Default")
      (node (ref "U1") (pin "AF25") (pinfunction "IO_L67N_1_AF25") (pintype "passive+no_connect"))
    )
    (net (code "237") (name "unconnected-(U1B-IO_L67P_1-PadAE24)") (class "Default")
      (node (ref "U1") (pin "AE24") (pinfunction "IO_L67P_1_AE24") (pintype "passive+no_connect"))
    )
    (net (code "238") (name "unconnected-(U1B-IO_L68N_1-PadW19)") (class "Default")
      (node (ref "U1") (pin "W19") (pinfunction "IO_L68N_1_W19") (pintype "passive+no_connect"))
    )
    (net (code "239") (name "unconnected-(U1B-IO_L68P_1-PadW18)") (class "Default")
      (node (ref "U1") (pin "W18") (pinfunction "IO_L68P_1_W18") (pintype "passive+no_connect"))
    )
    (net (code "240") (name "unconnected-(U1B-IO_L69N_VREF_1-PadAB22)") (class "Default")
      (node (ref "U1") (pin "AB22") (pinfunction "IO_L69N_VREF_1_AB22") (pintype "passive+no_connect"))
    )
    (net (code "241") (name "unconnected-(U1B-IO_L69P_1-PadAB21)") (class "Default")
      (node (ref "U1") (pin "AB21") (pinfunction "IO_L69P_1_AB21") (pintype "passive+no_connect"))
    )
    (net (code "242") (name "unconnected-(U1B-IO_L70N_1-PadV20)") (class "Default")
      (node (ref "U1") (pin "V20") (pinfunction "IO_L70N_1_V20") (pintype "passive+no_connect"))
    )
    (net (code "243") (name "unconnected-(U1B-IO_L70P_1-PadU19)") (class "Default")
      (node (ref "U1") (pin "U19") (pinfunction "IO_L70P_1_U19") (pintype "passive+no_connect"))
    )
    (net (code "244") (name "unconnected-(U1B-IO_L71N_1-PadW22)") (class "Default")
      (node (ref "U1") (pin "W22") (pinfunction "IO_L71N_1_W22") (pintype "passive+no_connect"))
    )
    (net (code "245") (name "unconnected-(U1B-IO_L71P_1-PadV22)") (class "Default")
      (node (ref "U1") (pin "V22") (pinfunction "IO_L71P_1_V22") (pintype "passive+no_connect"))
    )
    (net (code "246") (name "unconnected-(U1B-IO_L72N_1-PadY21)") (class "Default")
      (node (ref "U1") (pin "Y21") (pinfunction "IO_L72N_1_Y21") (pintype "passive+no_connect"))
    )
    (net (code "247") (name "unconnected-(U1B-IO_L72P_1-PadY20)") (class "Default")
      (node (ref "U1") (pin "Y20") (pinfunction "IO_L72P_1_Y20") (pintype "passive+no_connect"))
    )
    (net (code "248") (name "unconnected-(U1B-IO_L73N_1-PadAA22)") (class "Default")
      (node (ref "U1") (pin "AA22") (pinfunction "IO_L73N_1_AA22") (pintype "passive+no_connect"))
    )
    (net (code "249") (name "unconnected-(U1B-IO_L73P_1-PadY22)") (class "Default")
      (node (ref "U1") (pin "Y22") (pinfunction "IO_L73P_1_Y22") (pintype "passive+no_connect"))
    )
    (net (code "250") (name "unconnected-(U1B-IO_L74N_DOUT_BUSY_1-PadAF24)") (class "Default")
      (node (ref "U1") (pin "AF24") (pinfunction "IO_L74N_DOUT_BUSY_1_AF24") (pintype "passive+no_connect"))
    )
    (net (code "251") (name "unconnected-(U1B-IO_L74P_AWAKE_1-PadAE23)") (class "Default")
      (node (ref "U1") (pin "AE23") (pinfunction "IO_L74P_AWAKE_1_AE23") (pintype "passive+no_connect"))
    )
    (net (code "252") (name "unconnected-(U1F-IO_L2N_M5A14_5-PadG21)") (class "Default")
      (node (ref "U1") (pin "G21") (pinfunction "IO_L2N_M5A14_5_G21") (pintype "passive+no_connect"))
    )
    (net (code "253") (name "unconnected-(U1F-IO_L26P_5-PadL20)") (class "Default")
      (node (ref "U1") (pin "L20") (pinfunction "IO_L26P_5_L20") (pintype "passive+no_connect"))
    )
    (net (code "254") (name "unconnected-(U1F-IO_L27N_5-PadJ20)") (class "Default")
      (node (ref "U1") (pin "J20") (pinfunction "IO_L27N_5_J20") (pintype "passive+no_connect"))
    )
    (net (code "255") (name "unconnected-(U1F-IO_L27P_5-PadH19)") (class "Default")
      (node (ref "U1") (pin "H19") (pinfunction "IO_L27P_5_H19") (pintype "passive+no_connect"))
    )
  )
)
